# power.net
KiCad netlist of a schematic drawn in Altium Designer
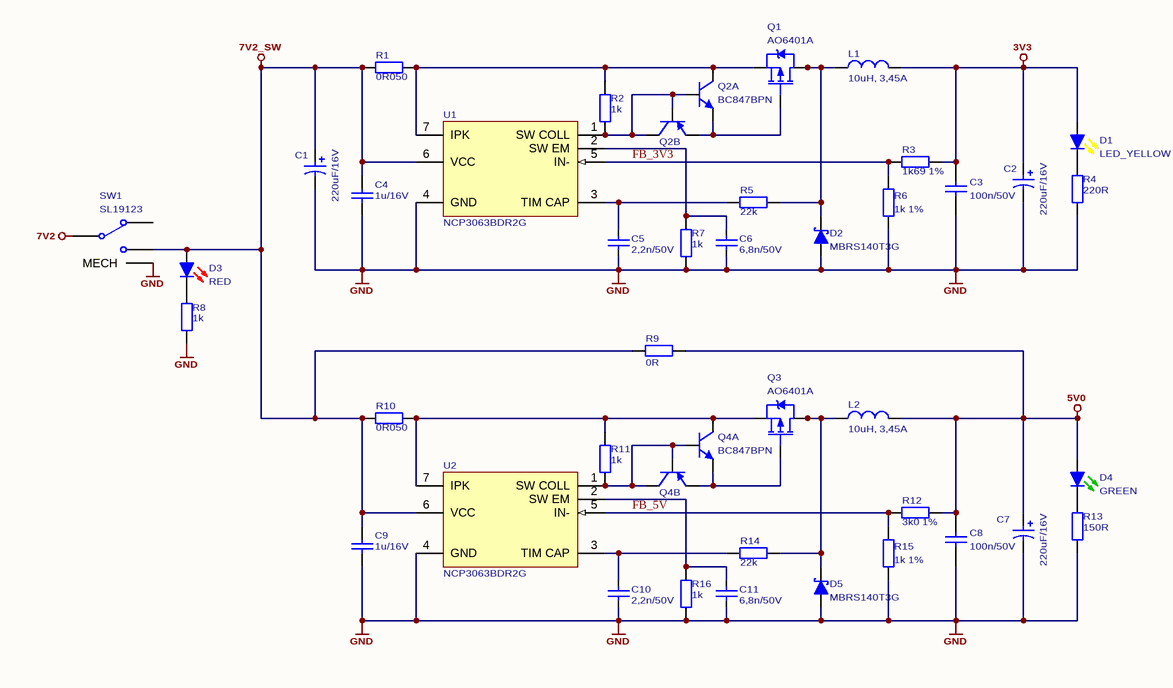
[diagram p0: power.SchDoc]

(export (version "E")
  (design (tool "Eeschema 10.0.6"))
  (components
    (comp (ref "C1")
      (value "220uF/16V")
      (footprint "CES_E_8.3x8.3_6.2")
      (description "Polarized Capacitor")
      (libsource (lib "capacitors") (part "Cap Pol"))
    )
    (comp (ref "C2")
      (value "220uF/16V")
      (footprint "CES_E_8.3x8.3_6.2")
      (description "Polarized Capacitor")
      (libsource (lib "capacitors") (part "Cap Pol"))
    )
    (comp (ref "C3")
      (value "100n/50V")
      (footprint "C0805")
      (description "Capacitor")
      (libsource (lib "capacitors") (part "Cap"))
    )
    (comp (ref "C4")
      (value "1u/16V")
      (footprint "C0805")
      (description "Capacitor")
      (libsource (lib "") (part "Cap_1"))
    )
    (comp (ref "C5")
      (value "2,2n/50V")
      (footprint "C0805")
      (description "Capacitor")
      (libsource (lib "") (part "Cap_2"))
    )
    (comp (ref "C6")
      (value "6,8n/50V")
      (footprint "C0805")
      (description "Capacitor")
      (libsource (lib "") (part "Cap_2"))
    )
    (comp (ref "C7")
      (value "220uF/16V")
      (footprint "CES_E_8.3x8.3_6.2")
      (description "Polarized Capacitor")
      (libsource (lib "capacitors") (part "Cap Pol"))
    )
    (comp (ref "C8")
      (value "100n/50V")
      (footprint "C0805")
      (description "Capacitor")
      (libsource (lib "capacitors") (part "Cap"))
    )
    (comp (ref "C9")
      (value "1u/16V")
      (footprint "C0805")
      (description "Capacitor")
      (libsource (lib "") (part "Cap_1"))
    )
    (comp (ref "C10")
      (value "2,2n/50V")
      (footprint "C0805")
      (description "Capacitor")
      (libsource (lib "") (part "Cap_2"))
    )
    (comp (ref "C11")
      (value "6,8n/50V")
      (footprint "C0805")
      (description "Capacitor")
      (libsource (lib "") (part "Cap_2"))
    )
    (comp (ref "D1")
      (value "LED_YELLOW")
      (footprint "LED0805Y")
      (description "YELLOW LED")
      (libsource (lib "leds") (part "LED_YELLOW"))
    )
    (comp (ref "D2")
      (value "MBRS140T3G")
      (footprint "SMB")
      (description "Schottky barrier rectifier: 40V, 1A")
      (libsource (lib "diodes_schottky") (part "MBRS140T3G"))
    )
    (comp (ref "D3")
      (value "RED")
      (footprint "LED0805R")
      (description "RED LED")
      (libsource (lib "leds") (part "LED_RED"))
    )
    (comp (ref "D4")
      (value "GREEN")
      (footprint "LED0805G")
      (description "GREEN LED")
      (libsource (lib "leds") (part "LED_GREEN"))
    )
    (comp (ref "D5")
      (value "MBRS140T3G")
      (footprint "SMB")
      (description "Schottky barrier rectifier: 40V, 1A")
      (libsource (lib "diodes_schottky") (part "MBRS140T3G"))
    )
    (comp (ref "L1")
      (value "10uH, 3,45A")
      (footprint "PSDB1005")
      (description "10uH, 20%, 3,45A, PSDB1005N Series Inductor")
      (libsource (lib "inductors") (part "PSDB1005NT100"))
    )
    (comp (ref "L2")
      (value "10uH, 3,45A")
      (footprint "PSDB1005")
      (description "10uH, 20%, 3,45A, PSDB1005N Series Inductor")
      (libsource (lib "inductors") (part "PSDB1005NT100"))
    )
    (comp (ref "Q1")
      (value "AO6401A")
      (footprint "SOT-23-6")
      (description "P-Channel MOSFET; -60V, -5A, 1.3W;")
      (libsource (lib "transistors_mos") (part "AO6401A"))
    )
    (comp (ref "Q2")
      (value "BC847BPN")
      (footprint "SOT-323-6 (SOT-363, SC88, SC70-6)")
      (description "PNP/NPN General Purpose Transistor (VCE=45V, IC=100mA)")
      (libsource (lib "transistors_bjt") (part "BC847BPN"))
    )
    (comp (ref "Q3")
      (value "AO6401A")
      (footprint "SOT-23-6")
      (description "P-Channel MOSFET; -60V, -5A, 1.3W;")
      (libsource (lib "transistors_mos") (part "AO6401A"))
    )
    (comp (ref "Q4")
      (value "BC847BPN")
      (footprint "SOT-323-6 (SOT-363, SC88, SC70-6)")
      (description "PNP/NPN General Purpose Transistor (VCE=45V, IC=100mA)")
      (libsource (lib "transistors_bjt") (part "BC847BPN"))
    )
    (comp (ref "R1")
      (value "0R050")
      (footprint "R0805")
      (description "Resistor")
      (libsource (lib "") (part "Res_1"))
    )
    (comp (ref "R2")
      (value "1k")
      (footprint "R0805")
      (description "Resistor")
      (libsource (lib "resistors") (part "Res"))
    )
    (comp (ref "R3")
      (value "1k69 1%")
      (footprint "R0805")
      (description "Resistor")
      (libsource (lib "") (part "Res_1"))
    )
    (comp (ref "R4")
      (value "220R")
      (footprint "R0805")
      (description "Resistor")
      (libsource (lib "resistors") (part "Res"))
    )
    (comp (ref "R5")
      (value "22k")
      (footprint "R0805")
      (description "Resistor")
      (libsource (lib "") (part "Res_2"))
    )
    (comp (ref "R6")
      (value "1k 1%")
      (footprint "R0805")
      (description "Resistor")
      (libsource (lib "resistors") (part "Res"))
    )
    (comp (ref "R7")
      (value "1k")
      (footprint "R0805")
      (description "Resistor")
      (libsource (lib "resistors") (part "Res"))
    )
    (comp (ref "R8")
      (value "1k")
      (footprint "R0805")
      (description "Resistor")
      (libsource (lib "resistors") (part "Res"))
    )
    (comp (ref "R9")
      (value "0R")
      (footprint "R1206")
      (description "Resistor")
      (libsource (lib "") (part "Res_3"))
    )
    (comp (ref "R10")
      (value "0R050")
      (footprint "R0805")
      (description "Resistor")
      (libsource (lib "") (part "Res_1"))
    )
    (comp (ref "R11")
      (value "1k")
      (footprint "R0805")
      (description "Resistor")
      (libsource (lib "resistors") (part "Res"))
    )
    (comp (ref "R12")
      (value "3k0 1%")
      (footprint "R0805")
      (description "Resistor")
      (libsource (lib "") (part "Res_1"))
    )
    (comp (ref "R13")
      (value "150R")
      (footprint "R0805")
      (description "Resistor")
      (libsource (lib "resistors") (part "Res"))
    )
    (comp (ref "R14")
      (value "22k")
      (footprint "R0805")
      (description "Resistor")
      (libsource (lib "") (part "Res_2"))
    )
    (comp (ref "R15")
      (value "1k 1%")
      (footprint "R0805")
      (description "Resistor")
      (libsource (lib "resistors") (part "Res"))
    )
    (comp (ref "R16")
      (value "1k")
      (footprint "R0805")
      (description "Resistor")
      (libsource (lib "resistors") (part "Res"))
    )
    (comp (ref "SW1")
      (value "SL19123")
      (footprint "500SSPxS1M6xEA")
      (description "Canal Electronic SPDT AC: 3A/250V, DC: 6A/28V")
      (libsource (lib "switches_slide") (part "SL19123"))
    )
    (comp (ref "U1")
      (value "NCP3063BDR2G")
      (footprint "SO8")
      (description "DC-DC Converter NCP3063BDR2G (Farnell 1547126)")
      (libsource (lib "switched_voltage_regulators") (part "NCP3063BDR2G"))
    )
    (comp (ref "U2")
      (value "NCP3063BDR2G")
      (footprint "SO8")
      (description "DC-DC Converter NCP3063BDR2G (Farnell 1547126)")
      (libsource (lib "switched_voltage_regulators") (part "NCP3063BDR2G"))
    )
  )
  (nets
    (net (code "1") (name "/FB_3V3") (class "Default")
      (node (ref "R3") (pin "1") (pinfunction "1_1") (pintype "passive"))
      (node (ref "R6") (pin "1") (pinfunction "1_1") (pintype "passive"))
      (node (ref "U1") (pin "5") (pinfunction "IN-_5") (pintype "input"))
    )
    (net (code "2") (name "/FB_5V") (class "Default")
      (node (ref "R12") (pin "1") (pinfunction "1_1") (pintype "passive"))
      (node (ref "R15") (pin "1") (pinfunction "1_1") (pintype "passive"))
      (node (ref "U2") (pin "5") (pinfunction "IN-_5") (pintype "input"))
    )
    (net (code "3") (name "3V3") (class "Default")
      (node (ref "C2") (pin "1") (pinfunction "1_1") (pintype "passive"))
      (node (ref "C3") (pin "2") (pinfunction "2_2") (pintype "passive"))
      (node (ref "D1") (pin "1") (pinfunction "A_1") (pintype "passive"))
      (node (ref "L1") (pin "2") (pinfunction "2_2") (pintype "passive"))
      (node (ref "R3") (pin "2") (pinfunction "2_2") (pintype "passive"))
    )
    (net (code "4") (name "5V0") (class "Default")
      (node (ref "C7") (pin "1") (pinfunction "1_1") (pintype "passive"))
      (node (ref "C8") (pin "2") (pinfunction "2_2") (pintype "passive"))
      (node (ref "D4") (pin "1") (pinfunction "A_1") (pintype "passive"))
      (node (ref "L2") (pin "2") (pinfunction "2_2") (pintype "passive"))
      (node (ref "R12") (pin "2") (pinfunction "2_2") (pintype "passive"))
      (node (ref "R9") (pin "2") (pinfunction "2_2") (pintype "passive"))
    )
    (net (code "5") (name "7V2") (class "Default")
      (node (ref "SW1") (pin "2") (pinfunction "2_2") (pintype "passive"))
    )
    (net (code "6") (name "7V2_SW") (class "Default")
      (node (ref "C1") (pin "1") (pinfunction "1_1") (pintype "passive"))
      (node (ref "C4") (pin "2") (pinfunction "2_2") (pintype "passive"))
      (node (ref "C9") (pin "2") (pinfunction "2_2") (pintype "passive"))
      (node (ref "D3") (pin "1") (pinfunction "A_1") (pintype "passive"))
      (node (ref "R1") (pin "1") (pinfunction "1_1") (pintype "passive"))
      (node (ref "R10") (pin "1") (pinfunction "1_1") (pintype "passive"))
      (node (ref "R9") (pin "1") (pinfunction "1_1") (pintype "passive"))
      (node (ref "SW1") (pin "3") (pinfunction "3_3") (pintype "passive"))
      (node (ref "U1") (pin "6") (pinfunction "VCC_6") (pintype "power_in"))
      (node (ref "U2") (pin "6") (pinfunction "VCC_6") (pintype "power_in"))
    )
    (net (code "7") (name "GND") (class "Default")
      (node (ref "C1") (pin "2") (pinfunction "2_2") (pintype "passive"))
      (node (ref "C10") (pin "1") (pinfunction "1_1") (pintype "passive"))
      (node (ref "C11") (pin "1") (pinfunction "1_1") (pintype "passive"))
      (node (ref "C2") (pin "2") (pinfunction "2_2") (pintype "passive"))
      (node (ref "C3") (pin "1") (pinfunction "1_1") (pintype "passive"))
      (node (ref "C4") (pin "1") (pinfunction "1_1") (pintype "passive"))
      (node (ref "C5") (pin "1") (pinfunction "1_1") (pintype "passive"))
      (node (ref "C6") (pin "1") (pinfunction "1_1") (pintype "passive"))
      (node (ref "C7") (pin "2") (pinfunction "2_2") (pintype "passive"))
      (node (ref "C8") (pin "1") (pinfunction "1_1") (pintype "passive"))
      (node (ref "C9") (pin "1") (pinfunction "1_1") (pintype "passive"))
      (node (ref "D2") (pin "1") (pinfunction "A_1") (pintype "passive"))
      (node (ref "D5") (pin "1") (pinfunction "A_1") (pintype "passive"))
      (node (ref "R13") (pin "2") (pinfunction "2_2") (pintype "passive"))
      (node (ref "R15") (pin "2") (pinfunction "2_2") (pintype "passive"))
      (node (ref "R16") (pin "2") (pinfunction "2_2") (pintype "passive"))
      (node (ref "R4") (pin "2") (pinfunction "2_2") (pintype "passive"))
      (node (ref "R6") (pin "2") (pinfunction "2_2") (pintype "passive"))
      (node (ref "R7") (pin "2") (pinfunction "2_2") (pintype "passive"))
      (node (ref "R8") (pin "2") (pinfunction "2_2") (pintype "passive"))
      (node (ref "SW1") (pin "M") (pinfunction "MECH_M") (pintype "passive"))
      (node (ref "U1") (pin "4") (pinfunction "GND_4") (pintype "power_in"))
      (node (ref "U2") (pin "4") (pinfunction "GND_4") (pintype "power_in"))
    )
    (net (code "8") (name "Net-(D1-K)") (class "Default")
      (node (ref "D1") (pin "2") (pinfunction "K_2") (pintype "passive"))
      (node (ref "R4") (pin "1") (pinfunction "1_1") (pintype "passive"))
    )
    (net (code "9") (name "Net-(D2-K)") (class "Default")
      (node (ref "D2") (pin "2") (pinfunction "K_2") (pintype "passive"))
      (node (ref "L1") (pin "1") (pinfunction "1_1") (pintype "passive"))
      (node (ref "Q1") (pin "1") (pinfunction "D_1") (pintype "passive"))
      (node (ref "Q1") (pin "2") (pinfunction "D_2") (pintype "passive"))
      (node (ref "Q1") (pin "5") (pinfunction "D_5") (pintype "passive"))
      (node (ref "Q1") (pin "6") (pinfunction "D_6") (pintype "passive"))
      (node (ref "R5") (pin "1") (pinfunction "1_1") (pintype "passive"))
    )
    (net (code "10") (name "Net-(D3-K)") (class "Default")
      (node (ref "D3") (pin "2") (pinfunction "K_2") (pintype "passive"))
      (node (ref "R8") (pin "1") (pinfunction "1_1") (pintype "passive"))
    )
    (net (code "11") (name "Net-(D4-K)") (class "Default")
      (node (ref "D4") (pin "2") (pinfunction "K_2") (pintype "passive"))
      (node (ref "R13") (pin "1") (pinfunction "1_1") (pintype "passive"))
    )
    (net (code "12") (name "Net-(D5-K)") (class "Default")
      (node (ref "D5") (pin "2") (pinfunction "K_2") (pintype "passive"))
      (node (ref "L2") (pin "1") (pinfunction "1_1") (pintype "passive"))
      (node (ref "Q3") (pin "1") (pinfunction "D_1") (pintype "passive"))
      (node (ref "Q3") (pin "2") (pinfunction "D_2") (pintype "passive"))
      (node (ref "Q3") (pin "5") (pinfunction "D_5") (pintype "passive"))
      (node (ref "Q3") (pin "6") (pinfunction "D_6") (pintype "passive"))
      (node (ref "R14") (pin "1") (pinfunction "1_1") (pintype "passive"))
    )
    (net (code "13") (name "Net-(Q1-G)") (class "Default")
      (node (ref "Q1") (pin "3") (pinfunction "G_3") (pintype "passive"))
      (node (ref "Q2") (pin "1") (pinfunction "EA_1") (pintype "passive"))
      (node (ref "Q2") (pin "4") (pinfunction "EB_4") (pintype "passive"))
    )
    (net (code "14") (name "Net-(Q1-S)") (class "Default")
      (node (ref "Q1") (pin "4") (pinfunction "S_4") (pintype "passive"))
      (node (ref "Q2") (pin "6") (pinfunction "CA_6") (pintype "passive"))
      (node (ref "R1") (pin "2") (pinfunction "2_2") (pintype "passive"))
      (node (ref "R2") (pin "1") (pinfunction "1_1") (pintype "passive"))
      (node (ref "U1") (pin "7") (pinfunction "IPK_7") (pintype "passive"))
    )
    (net (code "15") (name "Net-(Q2A-BA)") (class "Default")
      (node (ref "Q2") (pin "2") (pinfunction "BA_2") (pintype "passive"))
      (node (ref "Q2") (pin "3") (pinfunction "CB_3") (pintype "passive"))
      (node (ref "Q2") (pin "5") (pinfunction "BB_5") (pintype "passive"))
      (node (ref "R2") (pin "2") (pinfunction "2_2") (pintype "passive"))
      (node (ref "U1") (pin "1") (pinfunction "SW_COLL_1") (pintype "passive"))
    )
    (net (code "16") (name "Net-(Q3-G)") (class "Default")
      (node (ref "Q3") (pin "3") (pinfunction "G_3") (pintype "passive"))
      (node (ref "Q4") (pin "1") (pinfunction "EA_1") (pintype "passive"))
      (node (ref "Q4") (pin "4") (pinfunction "EB_4") (pintype "passive"))
    )
    (net (code "17") (name "Net-(Q3-S)") (class "Default")
      (node (ref "Q3") (pin "4") (pinfunction "S_4") (pintype "passive"))
      (node (ref "Q4") (pin "6") (pinfunction "CA_6") (pintype "passive"))
      (node (ref "R10") (pin "2") (pinfunction "2_2") (pintype "passive"))
      (node (ref "R11") (pin "1") (pinfunction "1_1") (pintype "passive"))
      (node (ref "U2") (pin "7") (pinfunction "IPK_7") (pintype "passive"))
    )
    (net (code "18") (name "Net-(Q4A-BA)") (class "Default")
      (node (ref "Q4") (pin "2") (pinfunction "BA_2") (pintype "passive"))
      (node (ref "Q4") (pin "3") (pinfunction "CB_3") (pintype "passive"))
      (node (ref "Q4") (pin "5") (pinfunction "BB_5") (pintype "passive"))
      (node (ref "R11") (pin "2") (pinfunction "2_2") (pintype "passive"))
      (node (ref "U2") (pin "1") (pinfunction "SW_COLL_1") (pintype "passive"))
    )
    (net (code "19") (name "Net-(U1-SW_EM)") (class "Default")
      (node (ref "C6") (pin "2") (pinfunction "2_2") (pintype "passive"))
      (node (ref "R7") (pin "1") (pinfunction "1_1") (pintype "passive"))
      (node (ref "U1") (pin "2") (pinfunction "SW_EM_2") (pintype "passive"))
    )
    (net (code "20") (name "Net-(U1-TIM_CAP)") (class "Default")
      (node (ref "C5") (pin "2") (pinfunction "2_2") (pintype "passive"))
      (node (ref "R5") (pin "2") (pinfunction "2_2") (pintype "passive"))
      (node (ref "U1") (pin "3") (pinfunction "TIM_CAP_3") (pintype "passive"))
    )
    (net (code "21") (name "Net-(U2-SW_EM)") (class "Default")
      (node (ref "C11") (pin "2") (pinfunction "2_2") (pintype "passive"))
      (node (ref "R16") (pin "1") (pinfunction "1_1") (pintype "passive"))
      (node (ref "U2") (pin "2") (pinfunction "SW_EM_2") (pintype "passive"))
    )
    (net (code "22") (name "Net-(U2-TIM_CAP)") (class "Default")
      (node (ref "C10") (pin "2") (pinfunction "2_2") (pintype "passive"))
      (node (ref "R14") (pin "2") (pinfunction "2_2") (pintype "passive"))
      (node (ref "U2") (pin "3") (pinfunction "TIM_CAP_3") (pintype "passive"))
    )
    (net (code "23") (name "unconnected-(SW1-Pad1)") (class "Default")
      (node (ref "SW1") (pin "1") (pinfunction "1_1") (pintype "passive"))
    )
  )
)
